# Schematic.net
KiCad netlist of a schematic drawn in EAGLE
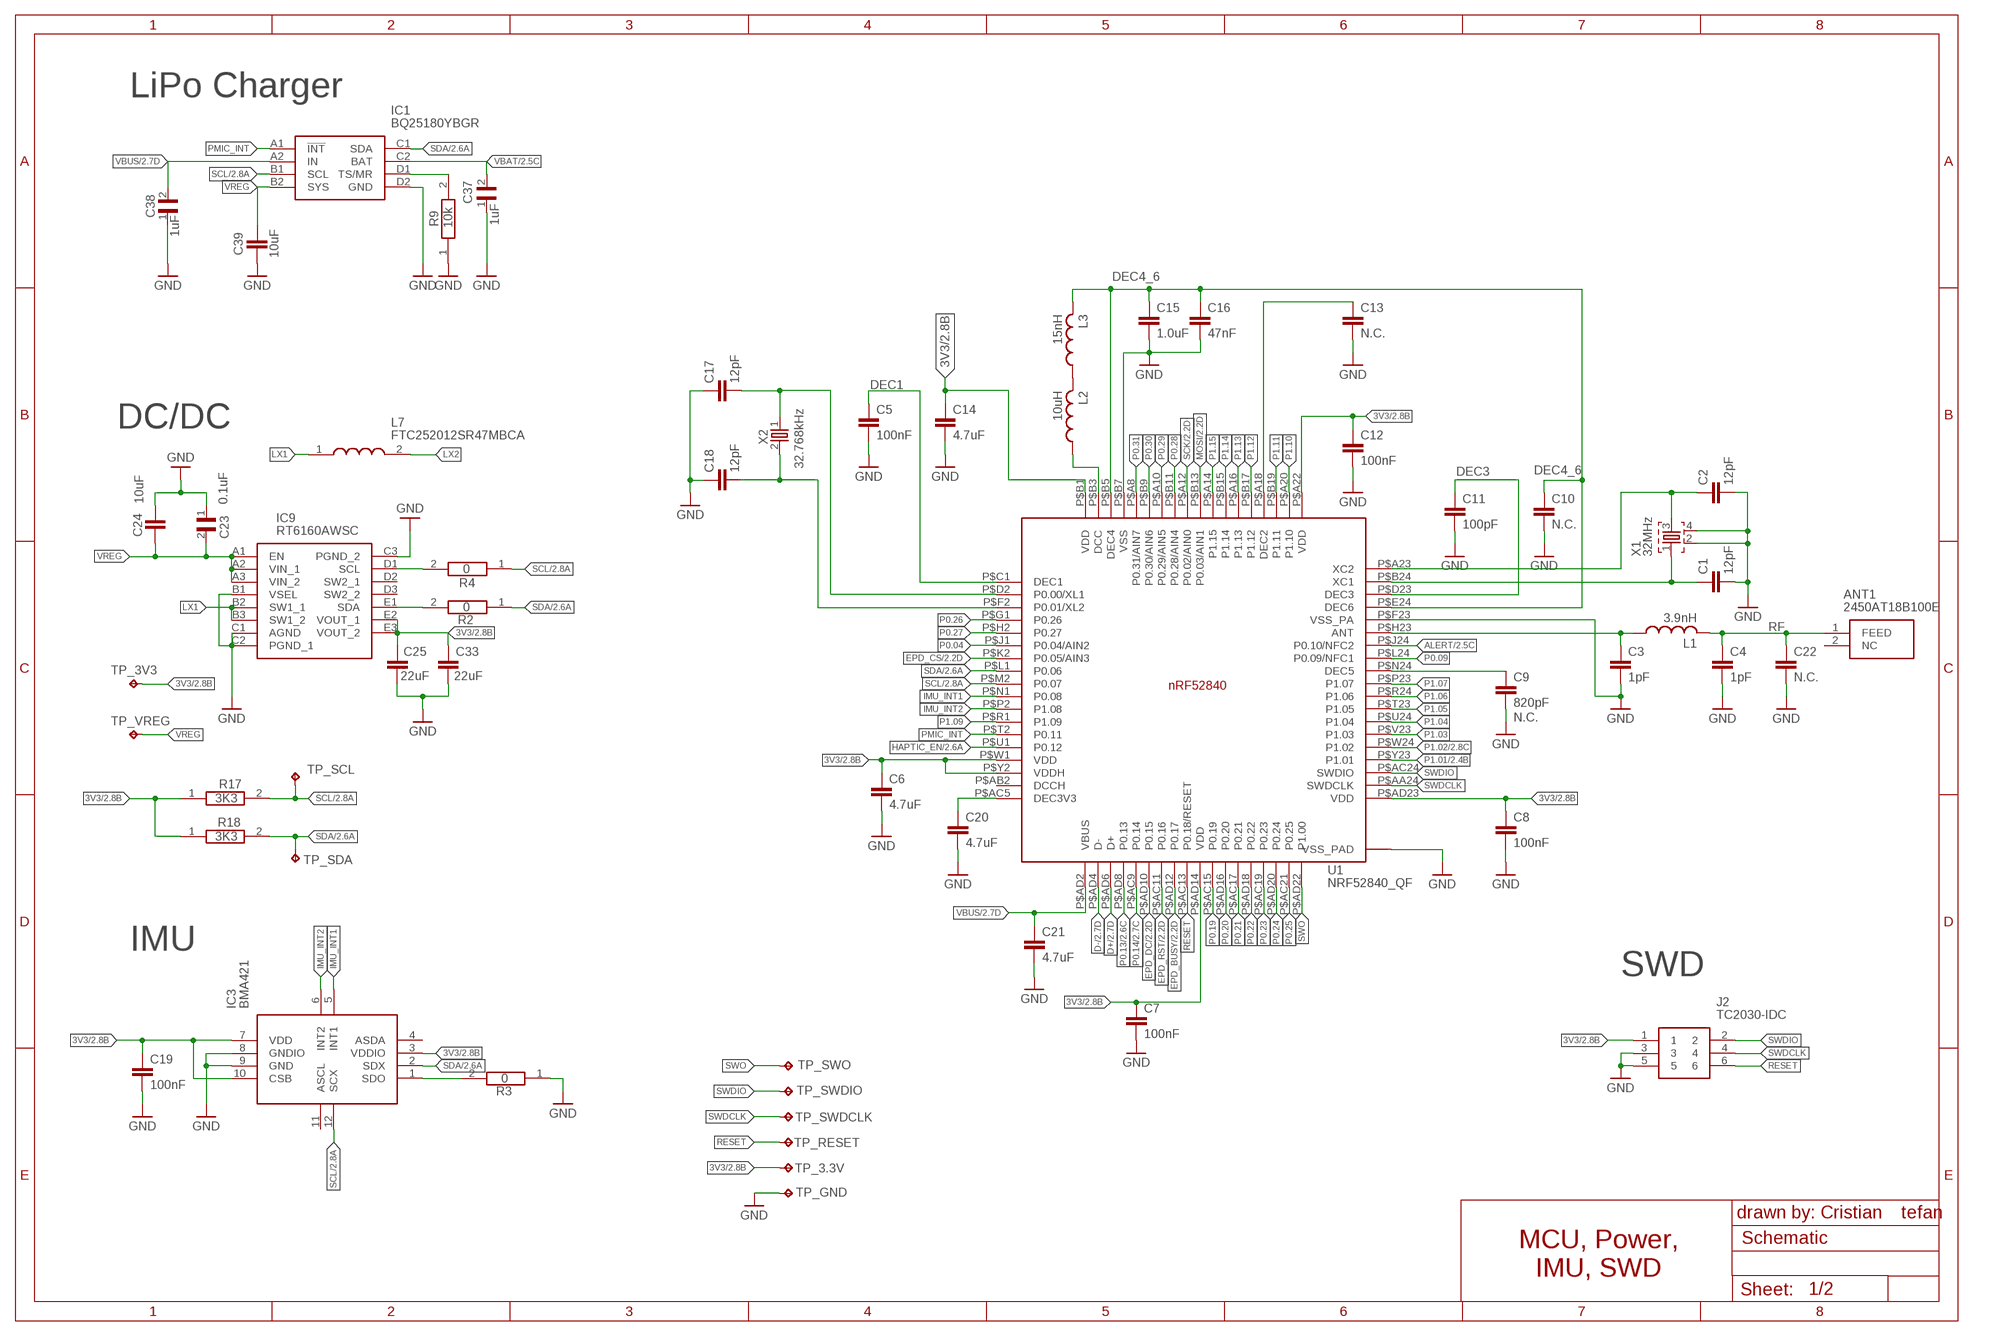
[diagram p0: schematic, sheet 1]
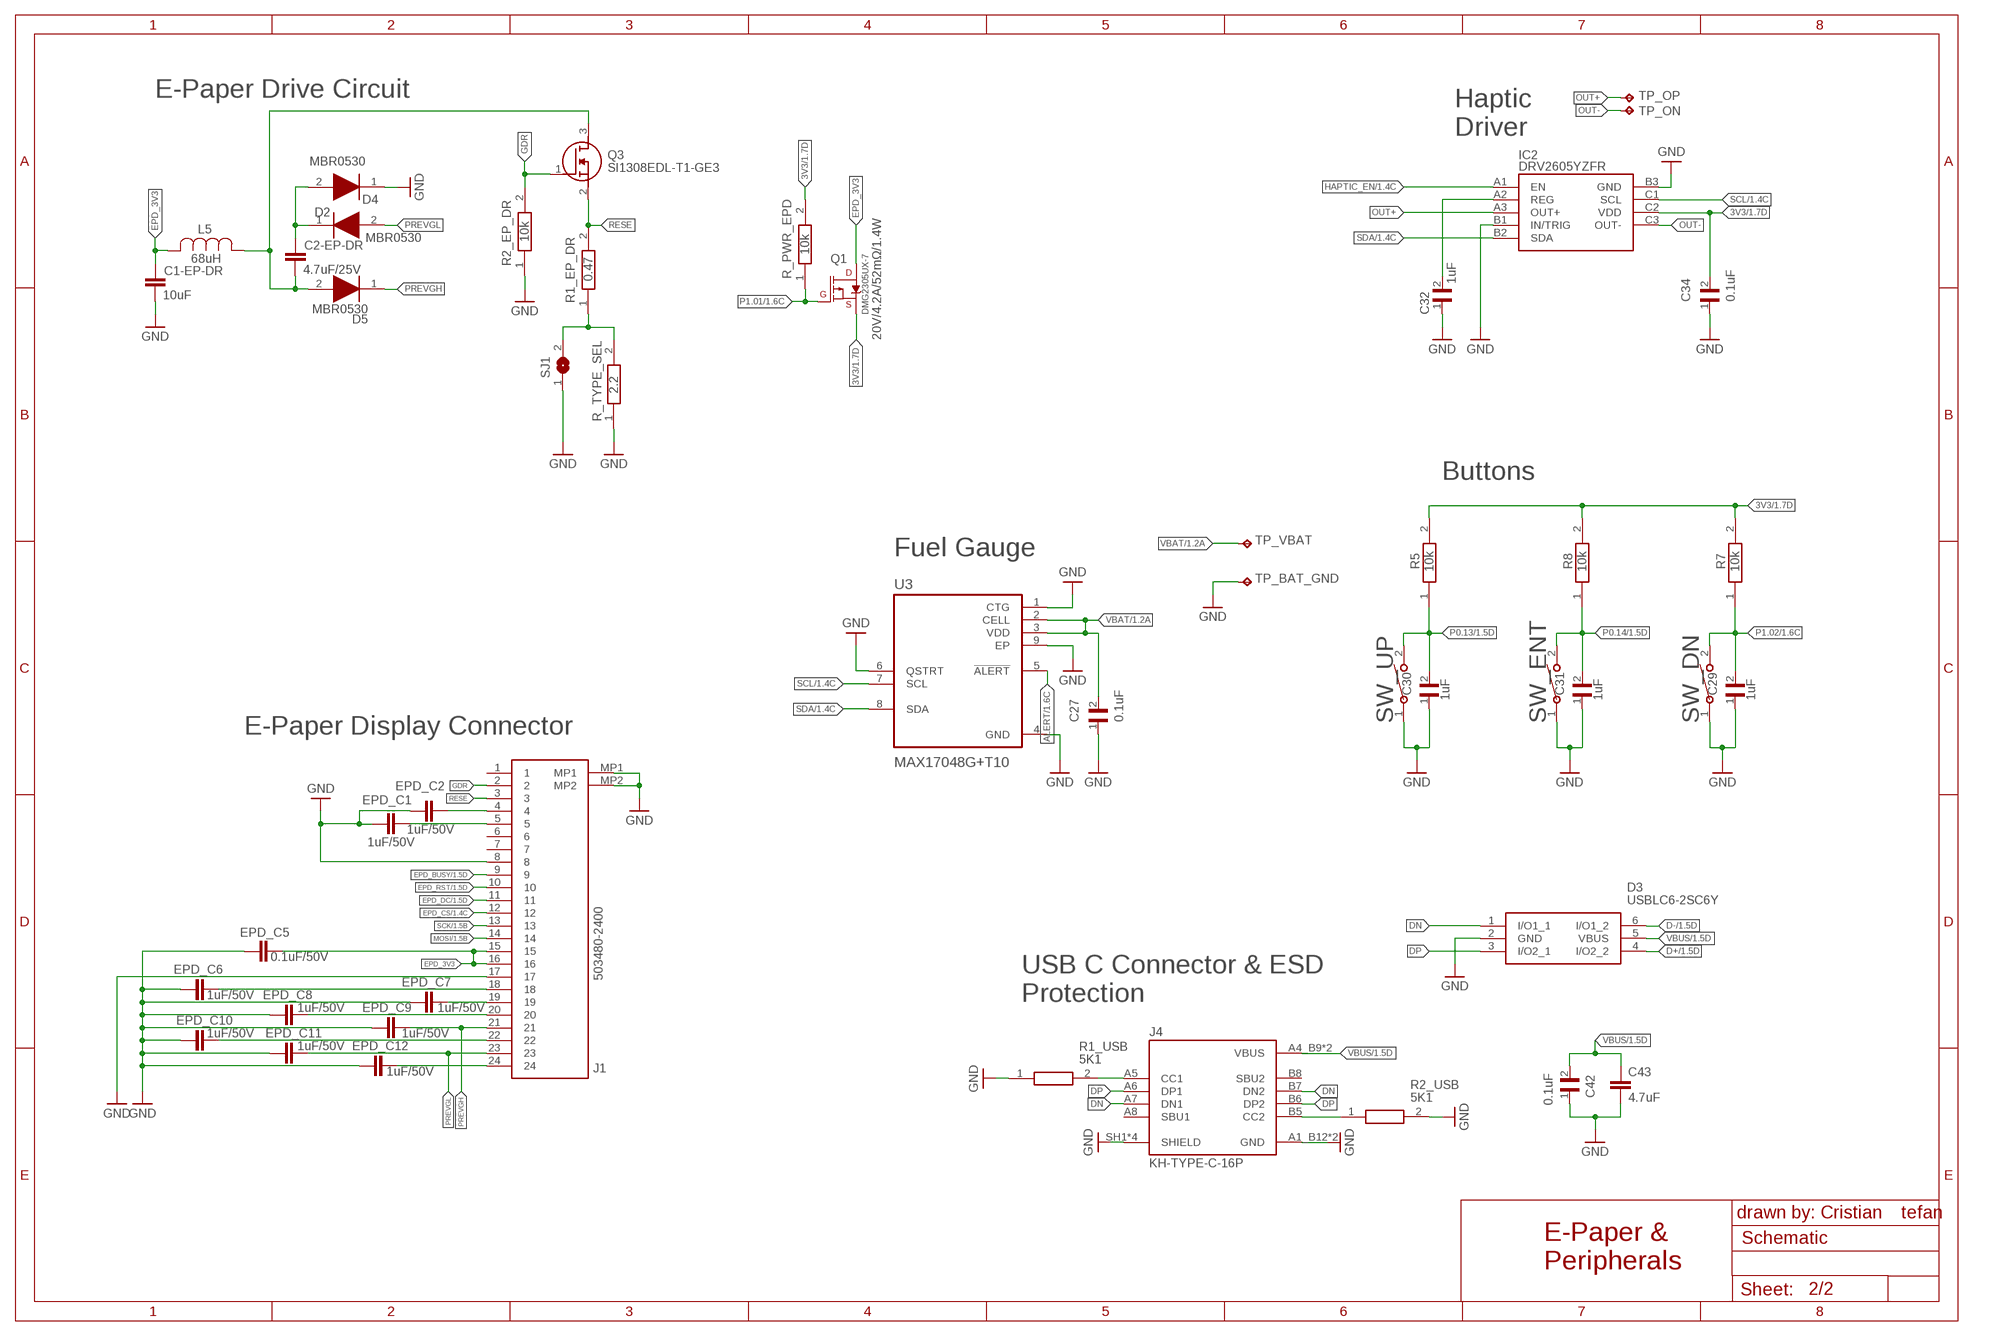
[diagram p1: schematic, sheet 2]

(export (version "E")
  (design (tool "Eeschema 10.0.6"))
  (components
    (comp (ref "ANT1")
      (value "2450AT18B100E")
      (footprint "eagle-import:2450AT18B100E_ANTC3216X140N")
      (fields (field (name "MOUSER_PART_NUMBER") "609-2450AT18B100E"))
      (libsource (lib "eagle-import") (part "2450AT18B100E_2450AT18B100E"))
    )
    (comp (ref "C1")
      (value "12pF")
      (footprint "eagle-import:NORDIC_NRF_3_RESC0201_L")
      (libsource (lib "eagle-import") (part "NORDIC_NRF_3_CAPACITOR_0201_L"))
    )
    (comp (ref "C2")
      (value "12pF")
      (footprint "eagle-import:NORDIC_NRF_3_RESC0201_L")
      (libsource (lib "eagle-import") (part "NORDIC_NRF_3_CAPACITOR_0201_L"))
    )
    (comp (ref "C3")
      (value "1pF")
      (footprint "eagle-import:NORDIC_NRF_3_RESC0201_L")
      (libsource (lib "eagle-import") (part "NORDIC_NRF_3_CAPACITOR_0201_L"))
    )
    (comp (ref "C4")
      (value "1pF")
      (footprint "eagle-import:NORDIC_NRF_3_RESC0201_L")
      (libsource (lib "eagle-import") (part "NORDIC_NRF_3_CAPACITOR_0201_L"))
    )
    (comp (ref "C5")
      (value "100nF")
      (footprint "eagle-import:NORDIC_NRF_3_RESC0201_L")
      (libsource (lib "eagle-import") (part "NORDIC_NRF_3_CAPACITOR_0201_L"))
    )
    (comp (ref "C6")
      (value "4.7uF")
      (footprint "eagle-import:NORDIC_NRF_3_RESC0402_L")
      (libsource (lib "eagle-import") (part "NORDIC_NRF_3_CAPACITOR_0402_L"))
    )
    (comp (ref "C7")
      (value "100nF")
      (footprint "eagle-import:NORDIC_NRF_3_RESC0201_L")
      (libsource (lib "eagle-import") (part "NORDIC_NRF_3_CAPACITOR_0201_L"))
    )
    (comp (ref "C8")
      (value "100nF")
      (footprint "eagle-import:NORDIC_NRF_3_RESC0201_L")
      (libsource (lib "eagle-import") (part "NORDIC_NRF_3_CAPACITOR_0201_L"))
    )
    (comp (ref "C9")
      (value "820pF")
      (footprint "eagle-import:NORDIC_NRF_3_RESC0201_L")
      (libsource (lib "eagle-import") (part "NORDIC_NRF_3_CAPACITOR_0201_L"))
    )
    (comp (ref "C10")
      (value "N.C.")
      (footprint "eagle-import:NORDIC_NRF_3_RESC0201_L")
      (libsource (lib "eagle-import") (part "NORDIC_NRF_3_CAPACITOR_0201_L"))
    )
    (comp (ref "C11")
      (value "100pF")
      (footprint "eagle-import:NORDIC_NRF_3_RESC0201_L")
      (libsource (lib "eagle-import") (part "NORDIC_NRF_3_CAPACITOR_0201_L"))
    )
    (comp (ref "C12")
      (value "100nF")
      (footprint "eagle-import:NORDIC_NRF_3_RESC0201_L")
      (libsource (lib "eagle-import") (part "NORDIC_NRF_3_CAPACITOR_0201_L"))
    )
    (comp (ref "C13")
      (value "N.C.")
      (footprint "eagle-import:NORDIC_NRF_3_RESC0201_L")
      (libsource (lib "eagle-import") (part "NORDIC_NRF_3_CAPACITOR_0201_L"))
    )
    (comp (ref "C14")
      (value "4.7uF")
      (footprint "eagle-import:NORDIC_NRF_3_RESC0402_L")
      (libsource (lib "eagle-import") (part "NORDIC_NRF_3_CAPACITOR_0402_L"))
    )
    (comp (ref "C15")
      (value "1.0uF")
      (footprint "eagle-import:NORDIC_NRF_3_RESC0402_L")
      (libsource (lib "eagle-import") (part "NORDIC_NRF_3_CAPACITOR_0402_L"))
    )
    (comp (ref "C16")
      (value "47nF")
      (footprint "eagle-import:NORDIC_NRF_3_RESC0201_L")
      (libsource (lib "eagle-import") (part "NORDIC_NRF_3_CAPACITOR_0201_L"))
    )
    (comp (ref "C17")
      (value "12pF")
      (footprint "eagle-import:NORDIC_NRF_3_RESC0201_L")
      (libsource (lib "eagle-import") (part "NORDIC_NRF_3_CAPACITOR_0201_L"))
    )
    (comp (ref "C18")
      (value "12pF")
      (footprint "eagle-import:NORDIC_NRF_3_RESC0201_L")
      (libsource (lib "eagle-import") (part "NORDIC_NRF_3_CAPACITOR_0201_L"))
    )
    (comp (ref "C19")
      (value "100nF")
      (footprint "eagle-import:NORDIC_NRF_3_RESC0201_L")
      (libsource (lib "eagle-import") (part "NORDIC_NRF_3_CAPACITOR_0201_L"))
    )
    (comp (ref "C20")
      (value "4.7uF")
      (footprint "eagle-import:NORDIC_NRF_3_RESC0402_L")
      (libsource (lib "eagle-import") (part "NORDIC_NRF_3_CAPACITOR_0402_L"))
    )
    (comp (ref "C21")
      (value "4.7uF")
      (footprint "eagle-import:NORDIC_NRF_3_RESC0402_L")
      (libsource (lib "eagle-import") (part "NORDIC_NRF_3_CAPACITOR_0402_L"))
    )
    (comp (ref "C22")
      (value "N.C.")
      (footprint "eagle-import:NORDIC_NRF_3_RESC0201_L")
      (libsource (lib "eagle-import") (part "NORDIC_NRF_3_CAPACITOR_0201_L"))
    )
    (comp (ref "C23")
      (value "0.1uF")
      (footprint "eagle-import:GRM011R60J152KE01L_2_CAPC0201X13N")
      (fields (field (name "MF") "Murata") (field (name "MP") "GRM011R60J152KE01L"))
      (libsource (lib "eagle-import") (part "GRM011R60J152KE01L_2_GRM011R60J152KE01L"))
    )
    (comp (ref "C24")
      (value "10uF")
      (footprint "eagle-import:NORDIC_NRF_3_RESC0402_L")
      (libsource (lib "eagle-import") (part "NORDIC_NRF_3_CAPACITOR_0402_L"))
    )
    (comp (ref "C25")
      (value "22uF")
      (footprint "eagle-import:NORDIC_NRF_3_RESC0402_L")
      (libsource (lib "eagle-import") (part "NORDIC_NRF_3_CAPACITOR_0402_L"))
    )
    (comp (ref "C33")
      (value "22uF")
      (footprint "eagle-import:NORDIC_NRF_3_RESC0402_L")
      (libsource (lib "eagle-import") (part "NORDIC_NRF_3_CAPACITOR_0402_L"))
    )
    (comp (ref "C37")
      (value "1uF")
      (footprint "eagle-import:GRM011R60J152KE01L_2_CAPC0201X13N")
      (fields (field (name "MF") "Murata") (field (name "MP") "GRM011R60J152KE01L"))
      (libsource (lib "eagle-import") (part "GRM011R60J152KE01L_2_GRM011R60J152KE01L"))
    )
    (comp (ref "C38")
      (value "1uF")
      (footprint "eagle-import:GRM011R60J152KE01L_2_CAPC0201X13N")
      (fields (field (name "MF") "Murata") (field (name "MP") "GRM011R60J152KE01L"))
      (libsource (lib "eagle-import") (part "GRM011R60J152KE01L_2_GRM011R60J152KE01L"))
    )
    (comp (ref "C39")
      (value "10uF")
      (footprint "eagle-import:NORDIC_NRF_3_RESC0402_L")
      (libsource (lib "eagle-import") (part "NORDIC_NRF_3_CAPACITOR_0402_L"))
    )
    (comp (ref "IC1")
      (value "BQ25180YBGR")
      (footprint "eagle-import:BQ25180YBGR_BGA8C40P2X4_100X155X50")
      (fields (field (name "MOUSER_PART_NUMBER") "595-BQ25180YBGR"))
      (libsource (lib "eagle-import") (part "BQ25180YBGR_BQ25180YBGR"))
    )
    (comp (ref "IC3")
      (value "BMA421")
      (footprint "eagle-import:BMA423_BMA423")
      (fields (field (name "ARROW_PART_NUMBER") "BMA423") (field (name "MOUSER_PART_NUMBER") "262-BMA423"))
      (libsource (lib "eagle-import") (part "BMA423_BMA423"))
    )
    (comp (ref "IC9")
      (value "RT6160AWSC")
      (footprint "eagle-import:RT6160AWSC_BGA15C40P3X5_140X230X60")
      (fields (field (name "MOUSER_PART_NUMBER") "835-RT6160AWSC"))
      (libsource (lib "eagle-import") (part "RT6160AWSC_RT6160AWSC"))
    )
    (comp (ref "J2")
      (value "TC2030-IDC")
      (footprint "eagle-import:TC2030-IDC_TC2030IDC")
      (libsource (lib "eagle-import") (part "TC2030-IDC_TC2030-IDC"))
    )
    (comp (ref "L1")
      (value "3.9nH")
      (footprint "eagle-import:NORDIC_NRF_2_RESC0402_L")
      (libsource (lib "eagle-import") (part "NORDIC_NRF_2_INDUCTOR_0402_L"))
    )
    (comp (ref "L2")
      (value "10uH")
      (footprint "eagle-import:NORDIC_NRF_2_RESC0201_L")
      (libsource (lib "eagle-import") (part "NORDIC_NRF_2_INDUCTOR_0201_L"))
    )
    (comp (ref "L3")
      (value "15nH")
      (footprint "eagle-import:NORDIC_NRF_2_RESC0201_L")
      (libsource (lib "eagle-import") (part "NORDIC_NRF_2_INDUCTOR_0201_L"))
    )
    (comp (ref "L7")
      (value "FTC252012SR47MBCA")
      (footprint "eagle-import:MLP2016SR47MT0S1_INDC2016X100N")
      (libsource (lib "eagle-import") (part "MLP2016SR47MT0S1_FTC252012SR47MBCA"))
    )
    (comp (ref "R2")
      (value "0")
      (footprint "eagle-import:CPF0201D7K68C1_0201")
      (libsource (lib "eagle-import") (part "CPF0201D7K68C1_CPF0201D7K68C1"))
    )
    (comp (ref "R3")
      (value "0")
      (footprint "eagle-import:CPF0201D7K68C1_0201")
      (libsource (lib "eagle-import") (part "CPF0201D7K68C1_CPF0201D7K68C1"))
    )
    (comp (ref "R4")
      (value "0")
      (footprint "eagle-import:CPF0201D7K68C1_0201")
      (libsource (lib "eagle-import") (part "CPF0201D7K68C1_CPF0201D7K68C1"))
    )
    (comp (ref "R9")
      (value "10k")
      (footprint "eagle-import:CPF0201D7K68C1_0201")
      (libsource (lib "eagle-import") (part "CPF0201D7K68C1_CPF0201D7K68C1"))
    )
    (comp (ref "R17")
      (value "3K3")
      (footprint "eagle-import:CPF0201D7K68C1_0201")
      (libsource (lib "eagle-import") (part "CPF0201D7K68C1_CPF0201D7K68C1"))
    )
    (comp (ref "R18")
      (value "3K3")
      (footprint "eagle-import:CPF0201D7K68C1_0201")
      (libsource (lib "eagle-import") (part "CPF0201D7K68C1_CPF0201D7K68C1"))
    )
    (comp (ref "TP_3.3V")
      (value "HECTOR_WATCH_1_TPTP20R")
      (footprint "eagle-import:HECTOR_WATCH_1_TP20R")
      (libsource (lib "eagle-import") (part "HECTOR_WATCH_1_TPTP20R"))
    )
    (comp (ref "TP_3V3")
      (value "HECTOR_WATCH_1_TPTP20R")
      (footprint "eagle-import:HECTOR_WATCH_1_TP20R")
      (libsource (lib "eagle-import") (part "HECTOR_WATCH_1_TPTP20R"))
    )
    (comp (ref "TP_GND")
      (value "HECTOR_WATCH_1_TPTP20R")
      (footprint "eagle-import:HECTOR_WATCH_1_TP20R")
      (libsource (lib "eagle-import") (part "HECTOR_WATCH_1_TPTP20R"))
    )
    (comp (ref "TP_RESET")
      (value "HECTOR_WATCH_1_TPTP20R")
      (footprint "eagle-import:HECTOR_WATCH_1_TP20R")
      (libsource (lib "eagle-import") (part "HECTOR_WATCH_1_TPTP20R"))
    )
    (comp (ref "TP_SCL")
      (value "HECTOR_WATCH_1_TPTP20R")
      (footprint "eagle-import:HECTOR_WATCH_1_TP20R")
      (libsource (lib "eagle-import") (part "HECTOR_WATCH_1_TPTP20R"))
    )
    (comp (ref "TP_SDA")
      (value "HECTOR_WATCH_1_TPTP20R")
      (footprint "eagle-import:HECTOR_WATCH_1_TP20R")
      (libsource (lib "eagle-import") (part "HECTOR_WATCH_1_TPTP20R"))
    )
    (comp (ref "TP_SWDCLK")
      (value "HECTOR_WATCH_1_TPTP20R")
      (footprint "eagle-import:HECTOR_WATCH_1_TP20R")
      (libsource (lib "eagle-import") (part "HECTOR_WATCH_1_TPTP20R"))
    )
    (comp (ref "TP_SWDIO")
      (value "HECTOR_WATCH_1_TPTP20R")
      (footprint "eagle-import:HECTOR_WATCH_1_TP20R")
      (libsource (lib "eagle-import") (part "HECTOR_WATCH_1_TPTP20R"))
    )
    (comp (ref "TP_SWO")
      (value "HECTOR_WATCH_1_TPTP20R")
      (footprint "eagle-import:HECTOR_WATCH_1_TP20R")
      (libsource (lib "eagle-import") (part "HECTOR_WATCH_1_TPTP20R"))
    )
    (comp (ref "TP_VREG")
      (value "HECTOR_WATCH_1_TPTP20R")
      (footprint "eagle-import:HECTOR_WATCH_1_TP20R")
      (libsource (lib "eagle-import") (part "HECTOR_WATCH_1_TPTP20R"))
    )
    (comp (ref "U1")
      (value "NRF52840_QF")
      (footprint "eagle-import:NORDIC_NRF_4_AQFN50P700X700X85_HS-74N")
      (libsource (lib "eagle-import") (part "NORDIC_NRF_4_NRF52840_QF"))
    )
    (comp (ref "X1")
      (value "32MHz")
      (footprint "eagle-import:NORDIC_NRF_BT-XTAL_2016_N")
      (libsource (lib "eagle-import") (part "NORDIC_NRF_XTAL_32MHZ"))
    )
    (comp (ref "X2")
      (value "32.768kHz")
      (footprint "eagle-import:NORDIC_NRF_1_XTAL_3215_N")
      (libsource (lib "eagle-import") (part "NORDIC_NRF_1_XTAL_32KHZ"))
    )
    (comp (ref "C1-EP-DR")
      (value "10uF")
      (footprint "eagle-import:NORDIC_NRF_3_RESC0402_L")
      (libsource (lib "eagle-import") (part "NORDIC_NRF_3_CAPACITOR_0402_L"))
    )
    (comp (ref "C2-EP-DR")
      (value "4.7uF/25V")
      (footprint "eagle-import:NORDIC_NRF_3_RESC0402_L")
      (libsource (lib "eagle-import") (part "NORDIC_NRF_3_CAPACITOR_0402_L"))
    )
    (comp (ref "C27")
      (value "0.1uF")
      (footprint "eagle-import:GRM011R60J152KE01L_2_CAPC0201X13N")
      (fields (field (name "MF") "Murata") (field (name "MP") "GRM011R60J152KE01L"))
      (libsource (lib "eagle-import") (part "GRM011R60J152KE01L_2_GRM011R60J152KE01L"))
    )
    (comp (ref "C29")
      (value "1uF")
      (footprint "eagle-import:GRM011R60J152KE01L_2_CAPC0201X13N")
      (fields (field (name "MF") "Murata") (field (name "MP") "GRM011R60J152KE01L"))
      (libsource (lib "eagle-import") (part "GRM011R60J152KE01L_2_GRM011R60J152KE01L"))
    )
    (comp (ref "C30")
      (value "1uF")
      (footprint "eagle-import:GRM011R60J152KE01L_2_CAPC0201X13N")
      (fields (field (name "MF") "Murata") (field (name "MP") "GRM011R60J152KE01L"))
      (libsource (lib "eagle-import") (part "GRM011R60J152KE01L_2_GRM011R60J152KE01L"))
    )
    (comp (ref "C31")
      (value "1uF")
      (footprint "eagle-import:GRM011R60J152KE01L_2_CAPC0201X13N")
      (fields (field (name "MF") "Murata") (field (name "MP") "GRM011R60J152KE01L"))
      (libsource (lib "eagle-import") (part "GRM011R60J152KE01L_2_GRM011R60J152KE01L"))
    )
    (comp (ref "C32")
      (value "1uF")
      (footprint "eagle-import:GRM011R60J152KE01L_2_CAPC0201X13N")
      (fields (field (name "MF") "Murata") (field (name "MP") "GRM011R60J152KE01L"))
      (libsource (lib "eagle-import") (part "GRM011R60J152KE01L_2_GRM011R60J152KE01L"))
    )
    (comp (ref "C34")
      (value "0.1uF")
      (footprint "eagle-import:GRM011R60J152KE01L_2_CAPC0201X13N")
      (fields (field (name "MF") "Murata") (field (name "MP") "GRM011R60J152KE01L"))
      (libsource (lib "eagle-import") (part "GRM011R60J152KE01L_2_GRM011R60J152KE01L"))
    )
    (comp (ref "C42")
      (value "0.1uF")
      (footprint "eagle-import:GRM011R60J152KE01L_2_CAPC0201X13N")
      (fields (field (name "MF") "Murata") (field (name "MP") "GRM011R60J152KE01L"))
      (libsource (lib "eagle-import") (part "GRM011R60J152KE01L_2_GRM011R60J152KE01L"))
    )
    (comp (ref "C43")
      (value "4.7uF")
      (footprint "eagle-import:NORDIC_NRF_3_RESC0402_L")
      (libsource (lib "eagle-import") (part "NORDIC_NRF_3_CAPACITOR_0402_L"))
    )
    (comp (ref "D2")
      (value "MBR0530")
      (footprint "eagle-import:ESP32_C6_LIBRARY_5_SOD3716X135N")
      (libsource (lib "eagle-import") (part "ESP32_C6_LIBRARY_5_MBR0530"))
    )
    (comp (ref "D3")
      (value "USBLC6-2SC6Y")
      (footprint "eagle-import:ESP32_C6_LIBRARY_3_SOT95P280X145-6N")
      (libsource (lib "eagle-import") (part "ESP32_C6_LIBRARY_3_USBLC6-2SC6Y"))
    )
    (comp (ref "D4")
      (value "MBR0530")
      (footprint "eagle-import:ESP32_C6_LIBRARY_5_SOD3716X135N")
      (libsource (lib "eagle-import") (part "ESP32_C6_LIBRARY_5_MBR0530"))
    )
    (comp (ref "D5")
      (value "MBR0530")
      (footprint "eagle-import:ESP32_C6_LIBRARY_5_SOD3716X135N")
      (libsource (lib "eagle-import") (part "ESP32_C6_LIBRARY_5_MBR0530"))
    )
    (comp (ref "EPD_C1")
      (value "1uF/50V")
      (footprint "eagle-import:NORDIC_NRF_3_RESC0402_L")
      (libsource (lib "eagle-import") (part "NORDIC_NRF_3_CAPACITOR_0402_L"))
    )
    (comp (ref "EPD_C2")
      (value "1uF/50V")
      (footprint "eagle-import:NORDIC_NRF_3_RESC0402_L")
      (libsource (lib "eagle-import") (part "NORDIC_NRF_3_CAPACITOR_0402_L"))
    )
    (comp (ref "EPD_C5")
      (value "0.1uF/50V")
      (footprint "eagle-import:NORDIC_NRF_3_RESC0402_L")
      (libsource (lib "eagle-import") (part "NORDIC_NRF_3_CAPACITOR_0402_L"))
    )
    (comp (ref "EPD_C6")
      (value "1uF/50V")
      (footprint "eagle-import:NORDIC_NRF_3_RESC0402_L")
      (libsource (lib "eagle-import") (part "NORDIC_NRF_3_CAPACITOR_0402_L"))
    )
    (comp (ref "EPD_C7")
      (value "1uF/50V")
      (footprint "eagle-import:NORDIC_NRF_3_RESC0402_L")
      (libsource (lib "eagle-import") (part "NORDIC_NRF_3_CAPACITOR_0402_L"))
    )
    (comp (ref "EPD_C8")
      (value "1uF/50V")
      (footprint "eagle-import:NORDIC_NRF_3_RESC0402_L")
      (libsource (lib "eagle-import") (part "NORDIC_NRF_3_CAPACITOR_0402_L"))
    )
    (comp (ref "EPD_C9")
      (value "1uF/50V")
      (footprint "eagle-import:NORDIC_NRF_3_RESC0402_L")
      (libsource (lib "eagle-import") (part "NORDIC_NRF_3_CAPACITOR_0402_L"))
    )
    (comp (ref "EPD_C10")
      (value "1uF/50V")
      (footprint "eagle-import:NORDIC_NRF_3_RESC0402_L")
      (libsource (lib "eagle-import") (part "NORDIC_NRF_3_CAPACITOR_0402_L"))
    )
    (comp (ref "EPD_C11")
      (value "1uF/50V")
      (footprint "eagle-import:NORDIC_NRF_3_RESC0402_L")
      (libsource (lib "eagle-import") (part "NORDIC_NRF_3_CAPACITOR_0402_L"))
    )
    (comp (ref "EPD_C12")
      (value "1uF/50V")
      (footprint "eagle-import:NORDIC_NRF_3_RESC0402_L")
      (libsource (lib "eagle-import") (part "NORDIC_NRF_3_CAPACITOR_0402_L"))
    )
    (comp (ref "IC2")
      (value "DRV2605YZFR")
      (footprint "eagle-import:DRV2605YZFR_BGA9C50P3X3_144X144X62")
      (libsource (lib "eagle-import") (part "DRV2605YZFR_DRV2605YZFR"))
    )
    (comp (ref "J1")
      (value "503480-2400")
      (footprint "eagle-import:503480-2400_5034802400")
      (fields (field (name "MOUSER_PART_NUMBER") "538-503480-2400"))
      (libsource (lib "eagle-import") (part "503480-2400_503480-2400"))
    )
    (comp (ref "J4")
      (value "KH-TYPE-C-16P")
      (footprint "eagle-import:KH-TYPE-C-16P_KINGHELM_KH-TYPE-C-16P")
      (fields (field (name "MF") "kinghelm"))
      (libsource (lib "eagle-import") (part "KH-TYPE-C-16P_KH-TYPE-C-16P"))
    )
    (comp (ref "L5")
      (value "68uH")
      (footprint "eagle-import:ESP32_C6_LIBRARY_2_IND_4828-WE-TPC_WRE")
      (fields
        (field (name "MANUFACTURER_PART_NUMBER") "744043680")
        (field (name "COPYRIGHT") "Copyright (C) 2024 Ultra Librarian. All rights reserved.")
      )
      (libsource (lib "eagle-import") (part "ESP32_C6_LIBRARY_2_744043680IND_4828-WE-TPC_WRE"))
    )
    (comp (ref "Q1")
      (value "20V/4.2A/52mΩ/1.4W")
      (footprint "eagle-import:ESP32_C6_LIBRARY_4_ESP32_C6_LIBRARY_4_ESP32_C6_LIBRARY_4_ESP32_C6_LIBRARY_4_ESP32_WROVER_SPARKFUN-DISCRETESEMI_SOT23-3")
      (libsource (lib "eagle-import") (part "ESP32_C6_LIBRARY_4_ESP32_WROVER_SPARKFUN-DISCRETESEMI_MOSFET_PCH-DMG2305UX-7"))
    )
    (comp (ref "Q3")
      (value "SI1308EDL-T1-GE3")
      (footprint "eagle-import:ESP32_C6_LIBRARY_6_SOT65P210X110-3N")
      (fields (field (name "MF") "Vishay Siliconix"))
      (libsource (lib "eagle-import") (part "ESP32_C6_LIBRARY_6_SI1308EDL-T1-GE3"))
    )
    (comp (ref "R1_EP_DR")
      (value "0.47")
      (footprint "eagle-import:CPF0201D7K68C1_0201")
      (libsource (lib "eagle-import") (part "CPF0201D7K68C1_CPF0201D7K68C1"))
    )
    (comp (ref "R1_USB")
      (value "5K1")
      (footprint "eagle-import:CPF0201D7K68C1_0201")
      (libsource (lib "eagle-import") (part "CPF0201D7K68C1_CPF0201D7K68C1"))
    )
    (comp (ref "R2_EP_DR")
      (value "10k")
      (footprint "eagle-import:CPF0201D7K68C1_0201")
      (libsource (lib "eagle-import") (part "CPF0201D7K68C1_CPF0201D7K68C1"))
    )
    (comp (ref "R2_USB")
      (value "5K1")
      (footprint "eagle-import:CPF0201D7K68C1_0201")
      (libsource (lib "eagle-import") (part "CPF0201D7K68C1_CPF0201D7K68C1"))
    )
    (comp (ref "R5")
      (value "10k")
      (footprint "eagle-import:CPF0201D7K68C1_0201")
      (libsource (lib "eagle-import") (part "CPF0201D7K68C1_CPF0201D7K68C1"))
    )
    (comp (ref "R7")
      (value "10k")
      (footprint "eagle-import:CPF0201D7K68C1_0201")
      (libsource (lib "eagle-import") (part "CPF0201D7K68C1_CPF0201D7K68C1"))
    )
    (comp (ref "R8")
      (value "10k")
      (footprint "eagle-import:CPF0201D7K68C1_0201")
      (libsource (lib "eagle-import") (part "CPF0201D7K68C1_CPF0201D7K68C1"))
    )
    (comp (ref "R_PWR_EPD")
      (value "10k")
      (footprint "eagle-import:CPF0201D7K68C1_0201")
      (libsource (lib "eagle-import") (part "CPF0201D7K68C1_CPF0201D7K68C1"))
    )
    (comp (ref "R_TYPE_SEL")
      (value "2.2")
      (footprint "eagle-import:CPF0201D7K68C1_0201")
      (libsource (lib "eagle-import") (part "CPF0201D7K68C1_CPF0201D7K68C1"))
    )
    (comp (ref "SJ1")
      (value "ESP32_C6_LIBRARY_7_JUMPER_SJ")
      (footprint "eagle-import:ESP32_C6_LIBRARY_7_JUMPER_SJ")
      (libsource (lib "eagle-import") (part "ESP32_C6_LIBRARY_7_JUMPER_SJ"))
    )
    (comp (ref "SW_DN")
      (value "2025-10-22_07-23-44_LIBRARY_EVP-AKE31A")
      (footprint "eagle-import:2025-10-22_07-23-44_LIBRARY_SW_EVP-AKE31A_PAN")
      (libsource (lib "eagle-import") (part "2025-10-22_07-23-44_LIBRARY_EVP-AKE31A"))
    )
    (comp (ref "SW_ENT")
      (value "2025-10-22_07-23-44_LIBRARY_EVP-AKE31A")
      (footprint "eagle-import:2025-10-22_07-23-44_LIBRARY_SW_EVP-AKE31A_PAN")
      (libsource (lib "eagle-import") (part "2025-10-22_07-23-44_LIBRARY_EVP-AKE31A"))
    )
    (comp (ref "SW_UP")
      (value "2025-10-22_07-23-44_LIBRARY_EVP-AKE31A")
      (footprint "eagle-import:2025-10-22_07-23-44_LIBRARY_SW_EVP-AKE31A_PAN")
      (libsource (lib "eagle-import") (part "2025-10-22_07-23-44_LIBRARY_EVP-AKE31A"))
    )
    (comp (ref "TP_BAT_GND")
      (value "HECTOR_WATCH_1_TPTP20R")
      (footprint "eagle-import:HECTOR_WATCH_1_TP20R")
      (libsource (lib "eagle-import") (part "HECTOR_WATCH_1_TPTP20R"))
    )
    (comp (ref "TP_ON")
      (value "HECTOR_WATCH_1_TPTP20R")
      (footprint "eagle-import:HECTOR_WATCH_1_TP20R")
      (libsource (lib "eagle-import") (part "HECTOR_WATCH_1_TPTP20R"))
    )
    (comp (ref "TP_OP")
      (value "HECTOR_WATCH_1_TPTP20R")
      (footprint "eagle-import:HECTOR_WATCH_1_TP20R")
      (libsource (lib "eagle-import") (part "HECTOR_WATCH_1_TPTP20R"))
    )
    (comp (ref "TP_VBAT")
      (value "HECTOR_WATCH_1_TPTP20R")
      (footprint "eagle-import:HECTOR_WATCH_1_TP20R")
      (libsource (lib "eagle-import") (part "HECTOR_WATCH_1_TPTP20R"))
    )
    (comp (ref "U3")
      (value "MAX17048G+T10")
      (footprint "eagle-import:ESP32_C6_LIBRARY_SON50P200X200X80-9N")
      (fields (field (name "MF") "Analog Devices"))
      (libsource (lib "eagle-import") (part "ESP32_C6_LIBRARY_MAX17048G+T10"))
    )
  )
  (nets
    (net (code "1") (name "3V3") (class "Default")
      (node (ref "C12") (pin "1") (pinfunction "1_1") (pintype "passive"))
      (node (ref "C14") (pin "1") (pinfunction "1_1") (pintype "passive"))
      (node (ref "C19") (pin "1") (pinfunction "1_1") (pintype "passive"))
      (node (ref "C25") (pin "2") (pinfunction "2_2") (pintype "passive"))
      (node (ref "C33") (pin "2") (pinfunction "2_2") (pintype "passive"))
      (node (ref "C34") (pin "2") (pinfunction "2_2") (pintype "passive"))
      (node (ref "C6") (pin "1") (pinfunction "1_1") (pintype "passive"))
      (node (ref "C7") (pin "1") (pinfunction "1_1") (pintype "passive"))
      (node (ref "C8") (pin "1") (pinfunction "1_1") (pintype "passive"))
      (node (ref "IC2") (pin "C2") (pinfunction "VDD_C2") (pintype "bidirectional"))
      (node (ref "IC3") (pin "10") (pinfunction "CSB_10") (pintype "bidirectional"))
      (node (ref "IC3") (pin "3") (pinfunction "VDDIO_3") (pintype "bidirectional"))
      (node (ref "IC3") (pin "7") (pinfunction "VDD_7") (pintype "bidirectional"))
      (node (ref "IC9") (pin "E2") (pinfunction "VOUT_1_E2") (pintype "bidirectional"))
      (node (ref "IC9") (pin "E3") (pinfunction "VOUT_2_E3") (pintype "bidirectional"))
      (node (ref "J2") (pin "1") (pinfunction "1_1") (pintype "bidirectional"))
      (node (ref "Q1") (pin "2") (pinfunction "S_2") (pintype "bidirectional"))
      (node (ref "R17") (pin "1") (pinfunction "1_1") (pintype "bidirectional"))
      (node (ref "R18") (pin "1") (pinfunction "1_1") (pintype "bidirectional"))
      (node (ref "R5") (pin "2") (pinfunction "2_2") (pintype "bidirectional"))
      (node (ref "R7") (pin "2") (pinfunction "2_2") (pintype "bidirectional"))
      (node (ref "R8") (pin "2") (pinfunction "2_2") (pintype "bidirectional"))
      (node (ref "R_PWR_EPD") (pin "2") (pinfunction "2_2") (pintype "bidirectional"))
      (node (ref "TP_3.3V") (pin "TP") (pinfunction "TP_TP") (pintype "input"))
      (node (ref "TP_3V3") (pin "TP") (pinfunction "TP_TP") (pintype "input"))
      (node (ref "U1") (pin "P$A22") (pinfunction "VDD_P$A22") (pintype "power_in"))
      (node (ref "U1") (pin "P$AD14") (pinfunction "VDD_P$AD14") (pintype "power_in"))
      (node (ref "U1") (pin "P$AD23") (pinfunction "VDD_P$AD23") (pintype "power_in"))
      (node (ref "U1") (pin "P$B1") (pinfunction "VDD_P$B1") (pintype "power_in"))
      (node (ref "U1") (pin "P$W1") (pinfunction "VDD_P$W1") (pintype "power_in"))
      (node (ref "U1") (pin "P$Y2") (pinfunction "VDDH_P$Y2") (pintype "power_in"))
    )
    (net (code "2") (name "ALERT") (class "Default")
      (node (ref "U1") (pin "P$J24") (pinfunction "P0.10/NFC2_P$J24") (pintype "bidirectional"))
      (node (ref "U3") (pin "5") (pinfunction "~{ALERT}_5") (pintype "output"))
    )
    (net (code "3") (name "D+") (class "Default")
      (node (ref "D3") (pin "4") (pinfunction "I/O2_2_4") (pintype "bidirectional"))
      (node (ref "U1") (pin "P$AD6") (pinfunction "D+_P$AD6") (pintype "bidirectional"))
    )
    (net (code "4") (name "D-") (class "Default")
      (node (ref "D3") (pin "6") (pinfunction "I/O1_2_6") (pintype "bidirectional"))
      (node (ref "U1") (pin "P$AD4") (pinfunction "D-_P$AD4") (pintype "bidirectional"))
    )
    (net (code "5") (name "DN") (class "Default")
      (node (ref "D3") (pin "1") (pinfunction "I/O1_1_1") (pintype "bidirectional"))
      (node (ref "J4") (pin "A7") (pinfunction "DN1_A7") (pintype "bidirectional"))
      (node (ref "J4") (pin "B7") (pinfunction "DN2_B7") (pintype "bidirectional"))
    )
    (net (code "6") (name "DP") (class "Default")
      (node (ref "D3") (pin "3") (pinfunction "I/O2_1_3") (pintype "bidirectional"))
      (node (ref "J4") (pin "A6") (pinfunction "DP1_A6") (pintype "bidirectional"))
      (node (ref "J4") (pin "B6") (pinfunction "DP2_B6") (pintype "bidirectional"))
    )
    (net (code "7") (name "EPD_3V3") (class "Default")
      (node (ref "C1-EP-DR") (pin "1") (pinfunction "1_1") (pintype "passive"))
      (node (ref "EPD_C5") (pin "2") (pinfunction "2_2") (pintype "passive"))
      (node (ref "J1") (pin "15") (pinfunction "15_15") (pintype "bidirectional"))
      (node (ref "J1") (pin "16") (pinfunction "16_16") (pintype "bidirectional"))
      (node (ref "L5") (pin "2") (pinfunction "2_2") (pintype "passive"))
      (node (ref "Q1") (pin "3") (pinfunction "D_3") (pintype "bidirectional"))
    )
    (net (code "8") (name "EPD_BUSY") (class "Default")
      (node (ref "J1") (pin "9") (pinfunction "9_9") (pintype "bidirectional"))
      (node (ref "U1") (pin "P$AD12") (pinfunction "P0.17_P$AD12") (pintype "bidirectional"))
    )
    (net (code "9") (name "EPD_CS") (class "Default")
      (node (ref "J1") (pin "12") (pinfunction "12_12") (pintype "bidirectional"))
      (node (ref "U1") (pin "P$K2") (pinfunction "P0.05/AIN3_P$K2") (pintype "bidirectional"))
    )
    (net (code "10") (name "EPD_DC") (class "Default")
      (node (ref "J1") (pin "11") (pinfunction "11_11") (pintype "bidirectional"))
      (node (ref "U1") (pin "P$AD10") (pinfunction "P0.15_P$AD10") (pintype "bidirectional"))
    )
    (net (code "11") (name "EPD_RST") (class "Default")
      (node (ref "J1") (pin "10") (pinfunction "10_10") (pintype "bidirectional"))
      (node (ref "U1") (pin "P$AC11") (pinfunction "P0.16_P$AC11") (pintype "bidirectional"))
    )
    (net (code "12") (name "GDR") (class "Default")
      (node (ref "J1") (pin "2") (pinfunction "2_2") (pintype "bidirectional"))
      (node (ref "Q3") (pin "1") (pinfunction "G_1") (pintype "bidirectional"))
      (node (ref "R2_EP_DR") (pin "2") (pinfunction "2_2") (pintype "bidirectional"))
    )
    (net (code "13") (name "GND") (class "Default")
      (node (ref "C1") (pin "2") (pinfunction "2_2") (pintype "passive"))
      (node (ref "C1-EP-DR") (pin "2") (pinfunction "2_2") (pintype "passive"))
      (node (ref "C10") (pin "2") (pinfunction "2_2") (pintype "passive"))
      (node (ref "C11") (pin "2") (pinfunction "2_2") (pintype "passive"))
      (node (ref "C12") (pin "2") (pinfunction "2_2") (pintype "passive"))
      (node (ref "C13") (pin "2") (pinfunction "2_2") (pintype "passive"))
      (node (ref "C14") (pin "2") (pinfunction "2_2") (pintype "passive"))
      (node (ref "C15") (pin "2") (pinfunction "2_2") (pintype "passive"))
      (node (ref "C16") (pin "2") (pinfunction "2_2") (pintype "passive"))
      (node (ref "C17") (pin "1") (pinfunction "1_1") (pintype "passive"))
      (node (ref "C18") (pin "1") (pinfunction "1_1") (pintype "passive"))
      (node (ref "C19") (pin "2") (pinfunction "2_2") (pintype "passive"))
      (node (ref "C2") (pin "2") (pinfunction "2_2") (pintype "passive"))
      (node (ref "C20") (pin "2") (pinfunction "2_2") (pintype "passive"))
      (node (ref "C21") (pin "2") (pinfunction "2_2") (pintype "passive"))
      (node (ref "C22") (pin "2") (pinfunction "2_2") (pintype "passive"))
      (node (ref "C23") (pin "1") (pinfunction "1_1") (pintype "passive"))
      (node (ref "C24") (pin "1") (pinfunction "1_1") (pintype "passive"))
      (node (ref "C25") (pin "1") (pinfunction "1_1") (pintype "passive"))
      (node (ref "C27") (pin "1") (pinfunction "1_1") (pintype "passive"))
      (node (ref "C29") (pin "1") (pinfunction "1_1") (pintype "passive"))
      (node (ref "C3") (pin "2") (pinfunction "2_2") (pintype "passive"))
      (node (ref "C30") (pin "1") (pinfunction "1_1") (pintype "passive"))
      (node (ref "C31") (pin "1") (pinfunction "1_1") (pintype "passive"))
      (node (ref "C32") (pin "1") (pinfunction "1_1") (pintype "passive"))
      (node (ref "C33") (pin "1") (pinfunction "1_1") (pintype "passive"))
      (node (ref "C34") (pin "1") (pinfunction "1_1") (pintype "passive"))
      (node (ref "C37") (pin "1") (pinfunction "1_1") (pintype "passive"))
      (node (ref "C38") (pin "1") (pinfunction "1_1") (pintype "passive"))
      (node (ref "C39") (pin "2") (pinfunction "2_2") (pintype "passive"))
      (node (ref "C4") (pin "2") (pinfunction "2_2") (pintype "passive"))
      (node (ref "C42") (pin "1") (pinfunction "1_1") (pintype "passive"))
      (node (ref "C43") (pin "2") (pinfunction "2_2") (pintype "passive"))
      (node (ref "C5") (pin "2") (pinfunction "2_2") (pintype "passive"))
      (node (ref "C6") (pin "2") (pinfunction "2_2") (pintype "passive"))
      (node (ref "C7") (pin "2") (pinfunction "2_2") (pintype "passive"))
      (node (ref "C8") (pin "2") (pinfunction "2_2") (pintype "passive"))
      (node (ref "C9") (pin "2") (pinfunction "2_2") (pintype "passive"))
      (node (ref "D3") (pin "2") (pinfunction "GND_2") (pintype "bidirectional"))
      (node (ref "D4") (pin "1") (pinfunction "K_1") (pintype "bidirectional"))
      (node (ref "EPD_C1") (pin "1") (pinfunction "1_1") (pintype "passive"))
      (node (ref "EPD_C10") (pin "1") (pinfunction "1_1") (pintype "passive"))
      (node (ref "EPD_C11") (pin "1") (pinfunction "1_1") (pintype "passive"))
      (node (ref "EPD_C12") (pin "1") (pinfunction "1_1") (pintype "passive"))
      (node (ref "EPD_C2") (pin "1") (pinfunction "1_1") (pintype "passive"))
      (node (ref "EPD_C5") (pin "1") (pinfunction "1_1") (pintype "passive"))
      (node (ref "EPD_C6") (pin "1") (pinfunction "1_1") (pintype "passive"))
      (node (ref "EPD_C7") (pin "1") (pinfunction "1_1") (pintype "passive"))
      (node (ref "EPD_C8") (pin "1") (pinfunction "1_1") (pintype "passive"))
      (node (ref "EPD_C9") (pin "1") (pinfunction "1_1") (pintype "passive"))
      (node (ref "IC1") (pin "D2") (pinfunction "GND_D2") (pintype "bidirectional"))
      (node (ref "IC2") (pin "B1") (pinfunction "IN/TRIG_B1") (pintype "bidirectional"))
      (node (ref "IC2") (pin "B3") (pinfunction "GND_B3") (pintype "bidirectional"))
      (node (ref "IC3") (pin "8") (pinfunction "GNDIO_8") (pintype "bidirectional"))
      (node (ref "IC3") (pin "9") (pinfunction "GND_9") (pintype "bidirectional"))
      (node (ref "IC9") (pin "B1") (pinfunction "VSEL_B1") (pintype "bidirectional"))
      (node (ref "IC9") (pin "C1") (pinfunction "AGND_C1") (pintype "bidirectional"))
      (node (ref "IC9") (pin "C2") (pinfunction "PGND_1_C2") (pintype "bidirectional"))
      (node (ref "IC9") (pin "C3") (pinfunction "PGND_2_C3") (pintype "bidirectional"))
      (node (ref "J1") (pin "17") (pinfunction "17_17") (pintype "bidirectional"))
      (node (ref "J1") (pin "8") (pinfunction "8_8") (pintype "bidirectional"))
      (node (ref "J1") (pin "MP1") (pinfunction "MP1_MP1") (pintype "bidirectional"))
      (node (ref "J1") (pin "MP2") (pinfunction "MP2_MP2") (pintype "bidirectional"))
      (node (ref "J2") (pin "3") (pinfunction "3_3") (pintype "bidirectional"))
      (node (ref "J2") (pin "5") (pinfunction "5_5") (pintype "bidirectional"))
      (node (ref "J4") (pin "A12_B1") (pinfunction "GND_A12_B1") (pintype "power_in"))
      (node (ref "J4") (pin "A1_B12") (pinfunction "GND_A1_B12") (pintype "power_in"))
      (node (ref "J4") (pin "SH1") (pinfunction "SHIELD_SH1") (pintype "passive"))
      (node (ref "J4") (pin "SH2") (pinfunction "SHIELD_SH2") (pintype "passive"))
      (node (ref "J4") (pin "SH3") (pinfunction "SHIELD_SH3") (pintype "passive"))
      (node (ref "J4") (pin "SH4") (pinfunction "SHIELD_SH4") (pintype "passive"))
      (node (ref "R1_USB") (pin "1") (pinfunction "1_1") (pintype "bidirectional"))
      (node (ref "R2_EP_DR") (pin "1") (pinfunction "1_1") (pintype "bidirectional"))
      (node (ref "R2_USB") (pin "2") (pinfunction "2_2") (pintype "bidirectional"))
      (node (ref "R3") (pin "1") (pinfunction "1_1") (pintype "bidirectional"))
      (node (ref "R9") (pin "1") (pinfunction "1_1") (pintype "bidirectional"))
      (node (ref "R_TYPE_SEL") (pin "1") (pinfunction "1_1") (pintype "bidirectional"))
      (node (ref "SJ1") (pin "1") (pinfunction "1_1") (pintype "passive"))
      (node (ref "SW_DN") (pin "1") (pinfunction "1_1") (pintype "passive"))
      (node (ref "SW_ENT") (pin "1") (pinfunction "1_1") (pintype "passive"))
      (node (ref "SW_UP") (pin "1") (pinfunction "1_1") (pintype "passive"))
      (node (ref "TP_BAT_GND") (pin "TP") (pinfunction "TP_TP") (pintype "input"))
      (node (ref "TP_GND") (pin "TP") (pinfunction "TP_TP") (pintype "input"))
      (node (ref "U1") (pin "P$74") (pinfunction "VSS_PAD_P$74") (pintype "bidirectional"))
      (node (ref "U1") (pin "P$75") (pinfunction "VSS_PAD_P$75") (pintype "bidirectional"))
      (node (ref "U1") (pin "P$76") (pinfunction "VSS_PAD_P$76") (pintype "bidirectional"))
      (node (ref "U1") (pin "P$77") (pinfunction "VSS_PAD_P$77") (pintype "bidirectional"))
      (node (ref "U1") (pin "P$78") (pinfunction "VSS_PAD_P$78") (pintype "bidirectional"))
      (node (ref "U1") (pin "P$79") (pinfunction "VSS_PAD_P$79") (pintype "bidirectional"))
      (node (ref "U1") (pin "P$80") (pinfunction "VSS_PAD_P$80") (pintype "bidirectional"))
      (node (ref "U1") (pin "P$81") (pinfunction "VSS_PAD_P$81") (pintype "bidirectional"))
      (node (ref "U1") (pin "P$82") (pinfunction "VSS_PAD_P$82") (pintype "bidirectional"))
      (node (ref "U1") (pin "P$83") (pinfunction "VSS_PAD_P$83") (pintype "bidirectional"))
      (node (ref "U1") (pin "P$84") (pinfunction "VSS_PAD_P$84") (pintype "bidirectional"))
      (node (ref "U1") (pin "P$85") (pinfunction "VSS_PAD_P$85") (pintype "bidirectional"))
      (node (ref "U1") (pin "P$86") (pinfunction "VSS_PAD_P$86") (pintype "bidirectional"))
      (node (ref "U1") (pin "P$87") (pinfunction "VSS_PAD_P$87") (pintype "bidirectional"))
      (node (ref "U1") (pin "P$88") (pinfunction "VSS_PAD_P$88") (pintype "bidirectional"))
      (node (ref "U1") (pin "P$89") (pinfunction "VSS_PAD_P$89") (pintype "bidirectional"))
      (node (ref "U1") (pin "P$90") (pinfunction "VSS_PAD_P$90") (pintype "bidirectional"))
      (node (ref "U1") (pin "P$B7") (pinfunction "VSS_P$B7") (pintype "power_in"))
      (node (ref "U1") (pin "P$F23") (pinfunction "VSS_PA_P$F23") (pintype "bidirectional"))
      (node (ref "U3") (pin "1") (pinfunction "CTG_1") (pintype "power_in"))
      (node (ref "U3") (pin "4") (pinfunction "GND_4") (pintype "power_in"))
      (node (ref "U3") (pin "6") (pinfunction "QSTRT_6") (pintype "input"))
      (node (ref "U3") (pin "9") (pinfunction "EP_9") (pintype "power_in"))
      (node (ref "X1") (pin "2") (pinfunction "2_2") (pintype "passive"))
      (node (ref "X1") (pin "4") (pinfunction "4_4") (pintype "passive"))
    )
    (net (code "14") (name "HAPTIC_EN") (class "Default")
      (node (ref "IC2") (pin "A1") (pinfunction "EN_A1") (pintype "bidirectional"))
      (node (ref "U1") (pin "P$U1") (pinfunction "P0.12_P$U1") (pintype "bidirectional"))
    )
    (net (code "15") (name "IMU_INT1") (class "Default")
      (node (ref "IC3") (pin "5") (pinfunction "INT1_5") (pintype "bidirectional"))
      (node (ref "U1") (pin "P$N1") (pinfunction "P0.08_P$N1") (pintype "bidirectional"))
    )
    (net (code "16") (name "IMU_INT2") (class "Default")
      (node (ref "IC3") (pin "6") (pinfunction "INT2_6") (pintype "bidirectional"))
      (node (ref "U1") (pin "P$P2") (pinfunction "P1.08_P$P2") (pintype "bidirectional"))
    )
    (net (code "17") (name "LX1") (class "Default")
      (node (ref "IC9") (pin "B2") (pinfunction "SW1_1_B2") (pintype "bidirectional"))
      (node (ref "IC9") (pin "B3") (pinfunction "SW1_2_B3") (pintype "bidirectional"))
      (node (ref "L7") (pin "1") (pinfunction "1_1") (pintype "bidirectional"))
    )
    (net (code "18") (name "LX2") (class "Default")
      (node (ref "L7") (pin "2") (pinfunction "2_2") (pintype "bidirectional"))
    )
    (net (code "19") (name "MOSI") (class "Default")
      (node (ref "J1") (pin "14") (pinfunction "14_14") (pintype "bidirectional"))
      (node (ref "U1") (pin "P$B13") (pinfunction "P0.03/AIN1_P$B13") (pintype "bidirectional"))
    )
    (net (code "20") (name "Net-(ANT1-FEED)") (class "Default")
      (node (ref "ANT1") (pin "1") (pinfunction "FEED_1") (pintype "input"))
      (node (ref "C22") (pin "1") (pinfunction "1_1") (pintype "passive"))
      (node (ref "C4") (pin "1") (pinfunction "1_1") (pintype "passive"))
      (node (ref "L1") (pin "2") (pinfunction "2_2") (pintype "passive"))
    )
    (net (code "21") (name "Net-(D2-K)") (class "Default")
      (node (ref "C2-EP-DR") (pin "1") (pinfunction "1_1") (pintype "passive"))
      (node (ref "D2") (pin "1") (pinfunction "K_1") (pintype "bidirectional"))
      (node (ref "D4") (pin "2") (pinfunction "A_2") (pintype "bidirectional"))
    )
    (net (code "22") (name "Net-(D5-A)") (class "Default")
      (node (ref "C2-EP-DR") (pin "2") (pinfunction "2_2") (pintype "passive"))
      (node (ref "D5") (pin "2") (pinfunction "A_2") (pintype "bidirectional"))
      (node (ref "L5") (pin "1") (pinfunction "1_1") (pintype "passive"))
      (node (ref "Q3") (pin "3") (pinfunction "D_3") (pintype "bidirectional"))
    )
    (net (code "23") (name "Net-(EPD_C1-Pad2)") (class "Default")
      (node (ref "EPD_C1") (pin "2") (pinfunction "2_2") (pintype "passive"))
      (node (ref "J1") (pin "5") (pinfunction "5_5") (pintype "bidirectional"))
    )
    (net (code "24") (name "Net-(EPD_C2-Pad2)") (class "Default")
      (node (ref "EPD_C2") (pin "2") (pinfunction "2_2") (pintype "passive"))
      (node (ref "J1") (pin "4") (pinfunction "4_4") (pintype "bidirectional"))
    )
    (net (code "25") (name "Net-(EPD_C6-Pad2)") (class "Default")
      (node (ref "EPD_C6") (pin "2") (pinfunction "2_2") (pintype "passive"))
      (node (ref "J1") (pin "18") (pinfunction "18_18") (pintype "bidirectional"))
    )
    (net (code "26") (name "Net-(EPD_C7-Pad2)") (class "Default")
      (node (ref "EPD_C7") (pin "2") (pinfunction "2_2") (pintype "passive"))
      (node (ref "J1") (pin "19") (pinfunction "19_19") (pintype "bidirectional"))
    )
    (net (code "27") (name "Net-(EPD_C8-Pad2)") (class "Default")
      (node (ref "EPD_C8") (pin "2") (pinfunction "2_2") (pintype "passive"))
      (node (ref "J1") (pin "20") (pinfunction "20_20") (pintype "bidirectional"))
    )
    (net (code "28") (name "Net-(EPD_C10-Pad2)") (class "Default")
      (node (ref "EPD_C10") (pin "2") (pinfunction "2_2") (pintype "passive"))
      (node (ref "J1") (pin "22") (pinfunction "22_22") (pintype "bidirectional"))
    )
    (net (code "29") (name "Net-(EPD_C12-Pad2)") (class "Default")
      (node (ref "EPD_C12") (pin "2") (pinfunction "2_2") (pintype "passive"))
      (node (ref "J1") (pin "24") (pinfunction "24_24") (pintype "bidirectional"))
    )
    (net (code "30") (name "Net-(IC1-TS{slash}MR)") (class "Default")
      (node (ref "IC1") (pin "D1") (pinfunction "TS/MR_D1") (pintype "bidirectional"))
      (node (ref "R9") (pin "2") (pinfunction "2_2") (pintype "bidirectional"))
    )
    (net (code "31") (name "Net-(IC2-REG)") (class "Default")
      (node (ref "C32") (pin "2") (pinfunction "2_2") (pintype "passive"))
      (node (ref "IC2") (pin "A2") (pinfunction "REG_A2") (pintype "bidirectional"))
    )
    (net (code "32") (name "Net-(IC3-SDO)") (class "Default")
      (node (ref "IC3") (pin "1") (pinfunction "SDO_1") (pintype "bidirectional"))
      (node (ref "R3") (pin "2") (pinfunction "2_2") (pintype "bidirectional"))
    )
    (net (code "33") (name "Net-(IC9-SCL)") (class "Default")
      (node (ref "IC9") (pin "D1") (pinfunction "SCL_D1") (pintype "bidirectional"))
      (node (ref "R4") (pin "2") (pinfunction "2_2") (pintype "bidirectional"))
    )
    (net (code "34") (name "Net-(IC9-SDA)") (class "Default")
      (node (ref "IC9") (pin "E1") (pinfunction "SDA_E1") (pintype "bidirectional"))
      (node (ref "R2") (pin "2") (pinfunction "2_2") (pintype "bidirectional"))
    )
    (net (code "35") (name "Net-(J4-CC1)") (class "Default")
      (node (ref "J4") (pin "A5") (pinfunction "CC1_A5") (pintype "bidirectional"))
      (node (ref "R1_USB") (pin "2") (pinfunction "2_2") (pintype "bidirectional"))
    )
    (net (code "36") (name "Net-(J4-CC2)") (class "Default")
      (node (ref "J4") (pin "B5") (pinfunction "CC2_B5") (pintype "bidirectional"))
      (node (ref "R2_USB") (pin "1") (pinfunction "1_1") (pintype "bidirectional"))
    )
    (net (code "37") (name "Net-(L2-Pad2)") (class "Default")
      (node (ref "L2") (pin "2") (pinfunction "2_2") (pintype "passive"))
      (node (ref "L3") (pin "1") (pinfunction "1_1") (pintype "passive"))
    )
    (net (code "38") (name "Net-(R1_EP_DR-Pad1)") (class "Default")
      (node (ref "R1_EP_DR") (pin "1") (pinfunction "1_1") (pintype "bidirectional"))
      (node (ref "R_TYPE_SEL") (pin "2") (pinfunction "2_2") (pintype "bidirectional"))
      (node (ref "SJ1") (pin "2") (pinfunction "2_2") (pintype "passive"))
    )
    (net (code "39") (name "Net-(U1-ANT)") (class "Default")
      (node (ref "C3") (pin "1") (pinfunction "1_1") (pintype "passive"))
      (node (ref "L1") (pin "1") (pinfunction "1_1") (pintype "passive"))
      (node (ref "U1") (pin "P$H23") (pinfunction "ANT_P$H23") (pintype "bidirectional"))
    )
    (net (code "40") (name "Net-(U1-DCC)") (class "Default")
      (node (ref "L2") (pin "1") (pinfunction "1_1") (pintype "passive"))
      (node (ref "U1") (pin "P$B3") (pinfunction "DCC_P$B3") (pintype "output"))
    )
    (net (code "41") (name "Net-(U1-DEC1)") (class "Default")
      (node (ref "C5") (pin "1") (pinfunction "1_1") (pintype "passive"))
      (node (ref "U1") (pin "P$C1") (pinfunction "DEC1_P$C1") (pintype "power_in"))
    )
    (net (code "42") (name "Net-(U1-DEC2)") (class "Default")
      (node (ref "C13") (pin "1") (pinfunction "1_1") (pintype "passive"))
      (node (ref "U1") (pin "P$A18") (pinfunction "DEC2_P$A18") (pintype "bidirectional"))
    )
    (net (code "43") (name "Net-(U1-DEC3)") (class "Default")
      (node (ref "C11") (pin "1") (pinfunction "1_1") (pintype "passive"))
      (node (ref "U1") (pin "P$D23") (pinfunction "DEC3_P$D23") (pintype "bidirectional"))
    )
    (net (code "44") (name "Net-(U1-DEC3V3)") (class "Default")
      (node (ref "C20") (pin "1") (pinfunction "1_1") (pintype "passive"))
      (node (ref "U1") (pin "P$AC5") (pinfunction "DEC3V3_P$AC5") (pintype "bidirectional"))
    )
    (net (code "45") (name "Net-(U1-DEC4)") (class "Default")
      (node (ref "C10") (pin "1") (pinfunction "1_1") (pintype "passive"))
      (node (ref "C15") (pin "1") (pinfunction "1_1") (pintype "passive"))
      (node (ref "C16") (pin "1") (pinfunction "1_1") (pintype "passive"))
      (node (ref "L3") (pin "2") (pinfunction "2_2") (pintype "passive"))
      (node (ref "U1") (pin "P$B5") (pinfunction "DEC4_P$B5") (pintype "power_in"))
      (node (ref "U1") (pin "P$E24") (pinfunction "DEC6_P$E24") (pintype "bidirectional"))
    )
    (net (code "46") (name "Net-(U1-DEC5)") (class "Default")
      (node (ref "C9") (pin "1") (pinfunction "1_1") (pintype "passive"))
      (node (ref "U1") (pin "P$N24") (pinfunction "DEC5_P$N24") (pintype "bidirectional"))
    )
    (net (code "47") (name "Net-(U1-P0.00{slash}XL1)") (class "Default")
      (node (ref "C17") (pin "2") (pinfunction "2_2") (pintype "passive"))
      (node (ref "U1") (pin "P$D2") (pinfunction "P0.00/XL1_P$D2") (pintype "bidirectional"))
      (node (ref "X2") (pin "1") (pinfunction "1_1") (pintype "passive"))
    )
    (net (code "48") (name "Net-(U1-P0.01{slash}XL2)") (class "Default")
      (node (ref "C18") (pin "2") (pinfunction "2_2") (pintype "passive"))
      (node (ref "U1") (pin "P$F2") (pinfunction "P0.01/XL2_P$F2") (pintype "bidirectional"))
      (node (ref "X2") (pin "2") (pinfunction "2_2") (pintype "passive"))
    )
    (net (code "49") (name "Net-(U1-XC1)") (class "Default")
      (node (ref "C1") (pin "1") (pinfunction "1_1") (pintype "passive"))
      (node (ref "U1") (pin "P$B24") (pinfunction "XC1_P$B24") (pintype "input"))
      (node (ref "X1") (pin "1") (pinfunction "1_1") (pintype "passive"))
    )
    (net (code "50") (name "Net-(U1-XC2)") (class "Default")
      (node (ref "C2") (pin "1") (pinfunction "1_1") (pintype "passive"))
      (node (ref "U1") (pin "P$A23") (pinfunction "XC2_P$A23") (pintype "output"))
      (node (ref "X1") (pin "3") (pinfunction "3_3") (pintype "passive"))
    )
    (net (code "51") (name "OUT+") (class "Default")
      (node (ref "IC2") (pin "A3") (pinfunction "OUT+_A3") (pintype "bidirectional"))
      (node (ref "TP_OP") (pin "TP") (pinfunction "TP_TP") (pintype "input"))
    )
    (net (code "52") (name "OUT-") (class "Default")
      (node (ref "IC2") (pin "C3") (pinfunction "OUT-_C3") (pintype "bidirectional"))
      (node (ref "TP_ON") (pin "TP") (pinfunction "TP_TP") (pintype "input"))
    )
    (net (code "53") (name "P0.04") (class "Default")
      (node (ref "U1") (pin "P$J1") (pinfunction "P0.04/AIN2_P$J1") (pintype "bidirectional"))
    )
    (net (code "54") (name "P0.09") (class "Default")
      (node (ref "U1") (pin "P$L24") (pinfunction "P0.09/NFC1_P$L24") (pintype "bidirectional"))
    )
    (net (code "55") (name "P0.13") (class "Default")
      (node (ref "C30") (pin "2") (pinfunction "2_2") (pintype "passive"))
      (node (ref "R5") (pin "1") (pinfunction "1_1") (pintype "bidirectional"))
      (node (ref "SW_UP") (pin "2") (pinfunction "2_2") (pintype "passive"))
      (node (ref "U1") (pin "P$AD8") (pinfunction "P0.13_P$AD8") (pintype "bidirectional"))
    )
    (net (code "56") (name "P0.14") (class "Default")
      (node (ref "C31") (pin "2") (pinfunction "2_2") (pintype "passive"))
      (node (ref "R8") (pin "1") (pinfunction "1_1") (pintype "bidirectional"))
      (node (ref "SW_ENT") (pin "2") (pinfunction "2_2") (pintype "passive"))
      (node (ref "U1") (pin "P$AC9") (pinfunction "P0.14_P$AC9") (pintype "bidirectional"))
    )
    (net (code "57") (name "P0.19") (class "Default")
      (node (ref "U1") (pin "P$AC15") (pinfunction "P0.19_P$AC15") (pintype "bidirectional"))
    )
    (net (code "58") (name "P0.20") (class "Default")
      (node (ref "U1") (pin "P$AD16") (pinfunction "P0.20_P$AD16") (pintype "bidirectional"))
    )
    (net (code "59") (name "P0.21") (class "Default")
      (node (ref "U1") (pin "P$AC17") (pinfunction "P0.21_P$AC17") (pintype "bidirectional"))
    )
    (net (code "60") (name "P0.22") (class "Default")
      (node (ref "U1") (pin "P$AD18") (pinfunction "P0.22_P$AD18") (pintype "bidirectional"))
    )
    (net (code "61") (name "P0.23") (class "Default")
      (node (ref "U1") (pin "P$AC19") (pinfunction "P0.23_P$AC19") (pintype "bidirectional"))
    )
    (net (code "62") (name "P0.24") (class "Default")
      (node (ref "U1") (pin "P$AD20") (pinfunction "P0.24_P$AD20") (pintype "bidirectional"))
    )
    (net (code "63") (name "P0.25") (class "Default")
      (node (ref "U1") (pin "P$AC21") (pinfunction "P0.25_P$AC21") (pintype "bidirectional"))
    )
    (net (code "64") (name "P0.26") (class "Default")
      (node (ref "U1") (pin "P$G1") (pinfunction "P0.26_P$G1") (pintype "bidirectional"))
    )
    (net (code "65") (name "P0.27") (class "Default")
      (node (ref "U1") (pin "P$H2") (pinfunction "P0.27_P$H2") (pintype "bidirectional"))
    )
    (net (code "66") (name "P0.28") (class "Default")
      (node (ref "U1") (pin "P$B11") (pinfunction "P0.28/AIN4_P$B11") (pintype "bidirectional"))
    )
    (net (code "67") (name "P0.29") (class "Default")
      (node (ref "U1") (pin "P$A10") (pinfunction "P0.29/AIN5_P$A10") (pintype "bidirectional"))
    )
    (net (code "68") (name "P0.30") (class "Default")
      (node (ref "U1") (pin "P$B9") (pinfunction "P0.30/AIN6_P$B9") (pintype "bidirectional"))
    )
    (net (code "69") (name "P0.31") (class "Default")
      (node (ref "U1") (pin "P$A8") (pinfunction "P0.31/AIN7_P$A8") (pintype "bidirectional"))
    )
    (net (code "70") (name "P1.01") (class "Default")
      (node (ref "Q1") (pin "1") (pinfunction "G_1") (pintype "bidirectional"))
      (node (ref "R_PWR_EPD") (pin "1") (pinfunction "1_1") (pintype "bidirectional"))
      (node (ref "U1") (pin "P$Y23") (pinfunction "P1.01_P$Y23") (pintype "bidirectional"))
    )
    (net (code "71") (name "P1.02") (class "Default")
      (node (ref "C29") (pin "2") (pinfunction "2_2") (pintype "passive"))
      (node (ref "R7") (pin "1") (pinfunction "1_1") (pintype "bidirectional"))
      (node (ref "SW_DN") (pin "2") (pinfunction "2_2") (pintype "passive"))
      (node (ref "U1") (pin "P$W24") (pinfunction "P1.02_P$W24") (pintype "bidirectional"))
    )
    (net (code "72") (name "P1.03") (class "Default")
      (node (ref "U1") (pin "P$V23") (pinfunction "P1.03_P$V23") (pintype "bidirectional"))
    )
    (net (code "73") (name "P1.04") (class "Default")
      (node (ref "U1") (pin "P$U24") (pinfunction "P1.04_P$U24") (pintype "bidirectional"))
    )
    (net (code "74") (name "P1.05") (class "Default")
      (node (ref "U1") (pin "P$T23") (pinfunction "P1.05_P$T23") (pintype "bidirectional"))
    )
    (net (code "75") (name "P1.06") (class "Default")
      (node (ref "U1") (pin "P$R24") (pinfunction "P1.06_P$R24") (pintype "bidirectional"))
    )
    (net (code "76") (name "P1.07") (class "Default")
      (node (ref "U1") (pin "P$P23") (pinfunction "P1.07_P$P23") (pintype "bidirectional"))
    )
    (net (code "77") (name "P1.09") (class "Default")
      (node (ref "U1") (pin "P$R1") (pinfunction "P1.09_P$R1") (pintype "bidirectional"))
    )
    (net (code "78") (name "P1.10") (class "Default")
      (node (ref "U1") (pin "P$A20") (pinfunction "P1.10_P$A20") (pintype "bidirectional"))
    )
    (net (code "79") (name "P1.11") (class "Default")
      (node (ref "U1") (pin "P$B19") (pinfunction "P1.11_P$B19") (pintype "bidirectional"))
    )
    (net (code "80") (name "P1.12") (class "Default")
      (node (ref "U1") (pin "P$B17") (pinfunction "P1.12_P$B17") (pintype "bidirectional"))
    )
    (net (code "81") (name "P1.13") (class "Default")
      (node (ref "U1") (pin "P$A16") (pinfunction "P1.13_P$A16") (pintype "bidirectional"))
    )
    (net (code "82") (name "P1.14") (class "Default")
      (node (ref "U1") (pin "P$B15") (pinfunction "P1.14_P$B15") (pintype "bidirectional"))
    )
    (net (code "83") (name "P1.15") (class "Default")
      (node (ref "U1") (pin "P$A14") (pinfunction "P1.15_P$A14") (pintype "bidirectional"))
    )
    (net (code "84") (name "PMIC_INT") (class "Default")
      (node (ref "IC1") (pin "A1") (pinfunction "~{INT}_A1") (pintype "bidirectional"))
      (node (ref "U1") (pin "P$T2") (pinfunction "P0.11_P$T2") (pintype "bidirectional"))
    )
    (net (code "85") (name "PREVGH") (class "Default")
      (node (ref "D5") (pin "1") (pinfunction "K_1") (pintype "bidirectional"))
      (node (ref "EPD_C9") (pin "2") (pinfunction "2_2") (pintype "passive"))
      (node (ref "J1") (pin "21") (pinfunction "21_21") (pintype "bidirectional"))
    )
    (net (code "86") (name "PREVGL") (class "Default")
      (node (ref "D2") (pin "2") (pinfunction "A_2") (pintype "bidirectional"))
      (node (ref "EPD_C11") (pin "2") (pinfunction "2_2") (pintype "passive"))
      (node (ref "J1") (pin "23") (pinfunction "23_23") (pintype "bidirectional"))
    )
    (net (code "87") (name "RESE") (class "Default")
      (node (ref "J1") (pin "3") (pinfunction "3_3") (pintype "bidirectional"))
      (node (ref "Q3") (pin "2") (pinfunction "S_2") (pintype "bidirectional"))
      (node (ref "R1_EP_DR") (pin "2") (pinfunction "2_2") (pintype "bidirectional"))
    )
    (net (code "88") (name "RESET") (class "Default")
      (node (ref "J2") (pin "6") (pinfunction "6_6") (pintype "bidirectional"))
      (node (ref "TP_RESET") (pin "TP") (pinfunction "TP_TP") (pintype "input"))
      (node (ref "U1") (pin "P$AC13") (pinfunction "P0.18/RESET_P$AC13") (pintype "bidirectional"))
    )
    (net (code "89") (name "SCK") (class "Default")
      (node (ref "J1") (pin "13") (pinfunction "13_13") (pintype "bidirectional"))
      (node (ref "U1") (pin "P$A12") (pinfunction "P0.02/AIN0_P$A12") (pintype "bidirectional"))
    )
    (net (code "90") (name "SCL") (class "Default")
      (node (ref "IC1") (pin "B1") (pinfunction "SCL_B1") (pintype "bidirectional"))
      (node (ref "IC2") (pin "C1") (pinfunction "SCL_C1") (pintype "bidirectional"))
      (node (ref "IC3") (pin "12") (pinfunction "SCX_12") (pintype "bidirectional"))
      (node (ref "R17") (pin "2") (pinfunction "2_2") (pintype "bidirectional"))
      (node (ref "R4") (pin "1") (pinfunction "1_1") (pintype "bidirectional"))
      (node (ref "TP_SCL") (pin "TP") (pinfunction "TP_TP") (pintype "input"))
      (node (ref "U1") (pin "P$M2") (pinfunction "P0.07_P$M2") (pintype "bidirectional"))
      (node (ref "U3") (pin "7") (pinfunction "SCL_7") (pintype "input"))
    )
    (net (code "91") (name "SDA") (class "Default")
      (node (ref "IC1") (pin "C1") (pinfunction "SDA_C1") (pintype "bidirectional"))
      (node (ref "IC2") (pin "B2") (pinfunction "SDA_B2") (pintype "bidirectional"))
      (node (ref "IC3") (pin "2") (pinfunction "SDX_2") (pintype "bidirectional"))
      (node (ref "R18") (pin "2") (pinfunction "2_2") (pintype "bidirectional"))
      (node (ref "R2") (pin "1") (pinfunction "1_1") (pintype "bidirectional"))
      (node (ref "TP_SDA") (pin "TP") (pinfunction "TP_TP") (pintype "input"))
      (node (ref "U1") (pin "P$L1") (pinfunction "P0.06_P$L1") (pintype "bidirectional"))
      (node (ref "U3") (pin "8") (pinfunction "SDA_8") (pintype "bidirectional"))
    )
    (net (code "92") (name "SWDCLK") (class "Default")
      (node (ref "J2") (pin "4") (pinfunction "4_4") (pintype "bidirectional"))
      (node (ref "TP_SWDCLK") (pin "TP") (pinfunction "TP_TP") (pintype "input"))
      (node (ref "U1") (pin "P$AA24") (pinfunction "SWDCLK_P$AA24") (pintype "input"))
    )
    (net (code "93") (name "SWDIO") (class "Default")
      (node (ref "J2") (pin "2") (pinfunction "2_2") (pintype "bidirectional"))
      (node (ref "TP_SWDIO") (pin "TP") (pinfunction "TP_TP") (pintype "input"))
      (node (ref "U1") (pin "P$AC24") (pinfunction "SWDIO_P$AC24") (pintype "bidirectional"))
    )
    (net (code "94") (name "SWO") (class "Default")
      (node (ref "TP_SWO") (pin "TP") (pinfunction "TP_TP") (pintype "input"))
      (node (ref "U1") (pin "P$AD22") (pinfunction "P1.00_P$AD22") (pintype "bidirectional"))
    )
    (net (code "95") (name "VBAT") (class "Default")
      (node (ref "C27") (pin "2") (pinfunction "2_2") (pintype "passive"))
      (node (ref "C37") (pin "2") (pinfunction "2_2") (pintype "passive"))
      (node (ref "IC1") (pin "C2") (pinfunction "BAT_C2") (pintype "bidirectional"))
      (node (ref "TP_VBAT") (pin "TP") (pinfunction "TP_TP") (pintype "input"))
      (node (ref "U3") (pin "2") (pinfunction "CELL_2") (pintype "power_in"))
      (node (ref "U3") (pin "3") (pinfunction "VDD_3") (pintype "power_in"))
    )
    (net (code "96") (name "VBUS") (class "Default")
      (node (ref "C21") (pin "1") (pinfunction "1_1") (pintype "passive"))
      (node (ref "C38") (pin "2") (pinfunction "2_2") (pintype "passive"))
      (node (ref "C42") (pin "2") (pinfunction "2_2") (pintype "passive"))
      (node (ref "C43") (pin "1") (pinfunction "1_1") (pintype "passive"))
      (node (ref "D3") (pin "5") (pinfunction "VBUS_5") (pintype "bidirectional"))
      (node (ref "IC1") (pin "A2") (pinfunction "IN_A2") (pintype "bidirectional"))
      (node (ref "J4") (pin "A4_B9") (pinfunction "VBUS_A4_B9") (pintype "power_in"))
      (node (ref "J4") (pin "A9_B4") (pinfunction "VBUS_A9_B4") (pintype "power_in"))
      (node (ref "U1") (pin "P$AD2") (pinfunction "VBUS_P$AD2") (pintype "power_in"))
    )
    (net (code "97") (name "VREG") (class "Default")
      (node (ref "C23") (pin "2") (pinfunction "2_2") (pintype "passive"))
      (node (ref "C24") (pin "2") (pinfunction "2_2") (pintype "passive"))
      (node (ref "C39") (pin "1") (pinfunction "1_1") (pintype "passive"))
      (node (ref "IC1") (pin "B2") (pinfunction "SYS_B2") (pintype "bidirectional"))
      (node (ref "IC9") (pin "A1") (pinfunction "EN_A1") (pintype "bidirectional"))
      (node (ref "IC9") (pin "A2") (pinfunction "VIN_1_A2") (pintype "bidirectional"))
      (node (ref "IC9") (pin "A3") (pinfunction "VIN_2_A3") (pintype "bidirectional"))
      (node (ref "TP_VREG") (pin "TP") (pinfunction "TP_TP") (pintype "input"))
    )
    (net (code "98") (name "unconnected-(ANT1-NC-Pad2)") (class "Default")
      (node (ref "ANT1") (pin "2") (pinfunction "NC_2") (pintype "no_connect"))
    )
    (net (code "99") (name "unconnected-(IC3-ASCL-Pad11)") (class "Default")
      (node (ref "IC3") (pin "11") (pinfunction "ASCL_11") (pintype "bidirectional"))
    )
    (net (code "100") (name "unconnected-(IC3-ASDA-Pad4)") (class "Default")
      (node (ref "IC3") (pin "4") (pinfunction "ASDA_4") (pintype "bidirectional"))
    )
    (net (code "101") (name "unconnected-(IC9-SW2_1-PadD2)") (class "Default")
      (node (ref "IC9") (pin "D2") (pinfunction "SW2_1_D2") (pintype "bidirectional"))
    )
    (net (code "102") (name "unconnected-(IC9-SW2_2-PadD3)") (class "Default")
      (node (ref "IC9") (pin "D3") (pinfunction "SW2_2_D3") (pintype "bidirectional"))
    )
    (net (code "103") (name "unconnected-(J1-Pad1)") (class "Default")
      (node (ref "J1") (pin "1") (pinfunction "1_1") (pintype "bidirectional"))
    )
    (net (code "104") (name "unconnected-(J1-Pad6)") (class "Default")
      (node (ref "J1") (pin "6") (pinfunction "6_6") (pintype "bidirectional"))
    )
    (net (code "105") (name "unconnected-(J1-Pad7)") (class "Default")
      (node (ref "J1") (pin "7") (pinfunction "7_7") (pintype "bidirectional"))
    )
    (net (code "106") (name "unconnected-(J4-SBU1-PadA8)") (class "Default")
      (node (ref "J4") (pin "A8") (pinfunction "SBU1_A8") (pintype "bidirectional"))
    )
    (net (code "107") (name "unconnected-(J4-SBU2-PadB8)") (class "Default")
      (node (ref "J4") (pin "B8") (pinfunction "SBU2_B8") (pintype "bidirectional"))
    )
    (net (code "108") (name "unconnected-(U1-DCCH-PadP$AB2)") (class "Default")
      (node (ref "U1") (pin "P$AB2") (pinfunction "DCCH_P$AB2") (pintype "bidirectional"))
    )
  )
)
